# sensors.net
KiCad netlist of a schematic drawn in Altium Designer
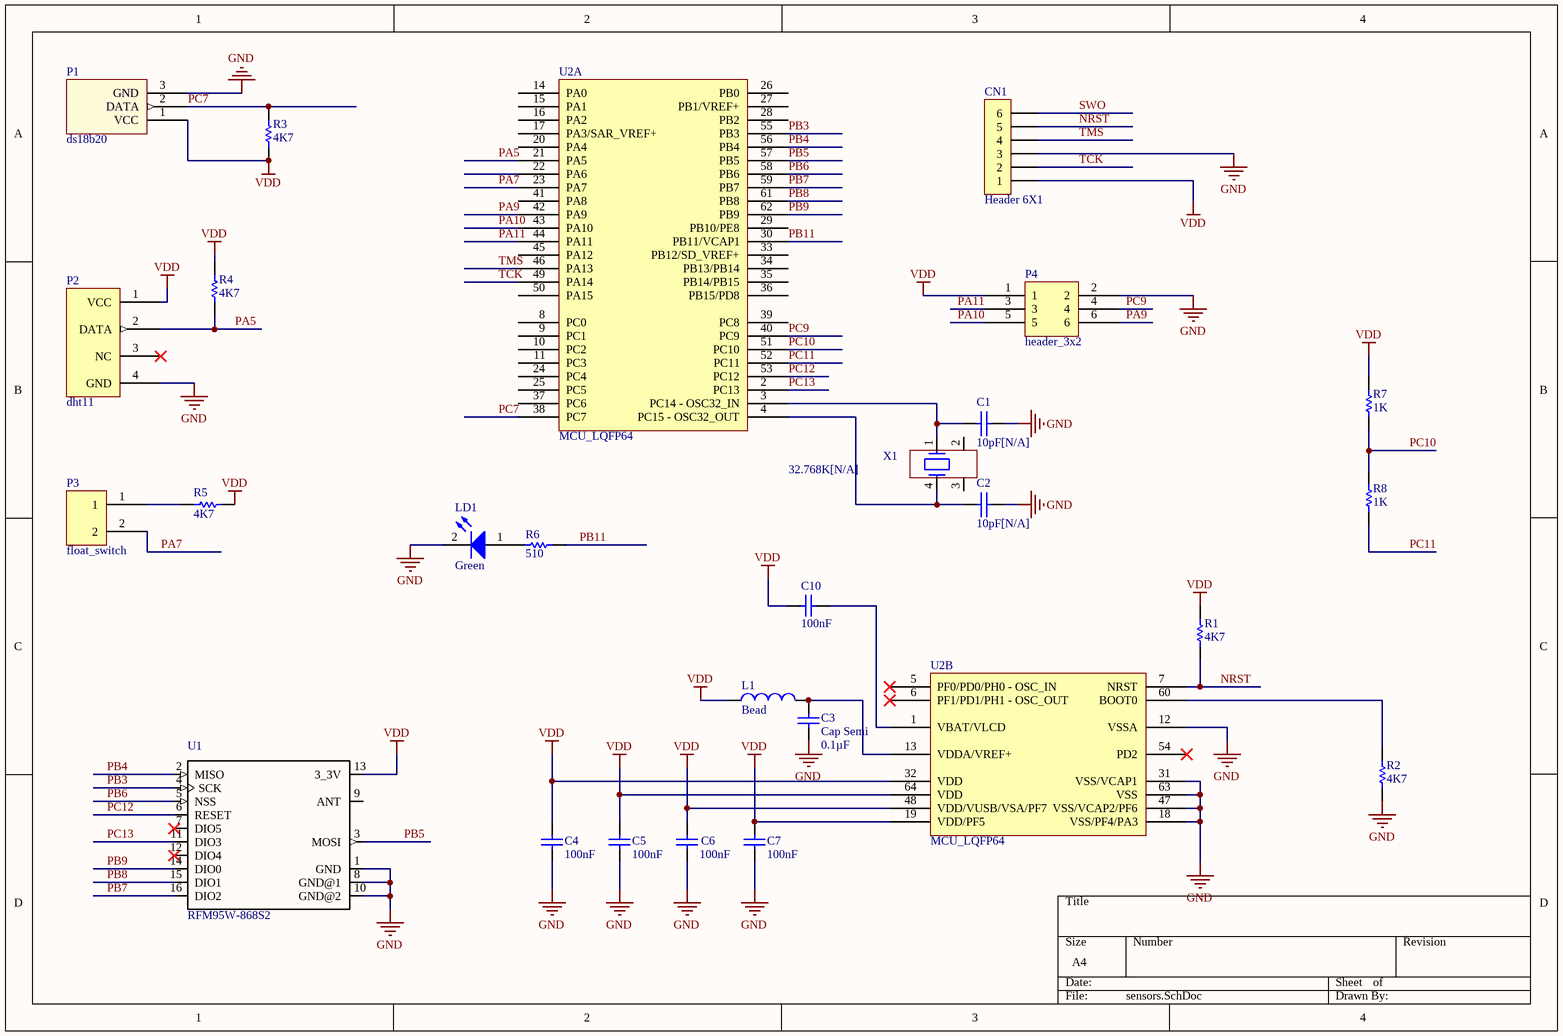
[diagram p0: sensors.SchDoc]

(export (version "E")
  (design (tool "Eeschema 10.0.6"))
  (components
    (comp (ref "C1")
      (value "10pF[N/A]")
      (footprint "0603C")
      (description "Capacitor")
      (fields (field (name "MANUFACTURER") "Murata Electronics North America"))
      (libsource (lib "MB1136") (part "CAP"))
    )
    (comp (ref "C2")
      (value "10pF[N/A]")
      (footprint "0603C")
      (description "Capacitor")
      (fields (field (name "MANUFACTURER") "Murata Electronics North America"))
      (libsource (lib "*") (part "CAP"))
    )
    (comp (ref "C3")
      (value "Cap Semi")
      (footprint "1608[0603]")
      (description "Capacitor (Semiconductor SIM Model)")
      (fields
        (field (name "ALTIUM_VALUE") "0.1µF")
        (field (name "MANUFACTURER") "AVX Corporation")
        (field (name "PUBLISHER") "Altium Limited")
      )
      (libsource (lib "Miscellaneous Devices") (part "Cap Semi"))
    )
    (comp (ref "C4")
      (value "100nF")
      (footprint "0603C")
      (description "Capacitor")
      (fields (field (name "MANUFACTURER") "AVX Corporation") (field (name "PUBLISHER") "Altium Limited"))
      (libsource (lib "Miscellaneous Devices") (part "Cap"))
    )
    (comp (ref "C5")
      (value "100nF")
      (footprint "0603C")
      (description "Capacitor")
      (fields (field (name "MANUFACTURER") "AVX Corporation") (field (name "PUBLISHER") "Altium Limited"))
      (libsource (lib "Miscellaneous Devices") (part "Cap"))
    )
    (comp (ref "C6")
      (value "100nF")
      (footprint "0603C")
      (description "Capacitor")
      (fields (field (name "MANUFACTURER") "AVX Corporation") (field (name "PUBLISHER") "Altium Limited"))
      (libsource (lib "Miscellaneous Devices") (part "Cap"))
    )
    (comp (ref "C7")
      (value "100nF")
      (footprint "0603C")
      (description "Capacitor")
      (fields (field (name "MANUFACTURER") "AVX Corporation") (field (name "PUBLISHER") "Altium Limited"))
      (libsource (lib "Miscellaneous Devices") (part "Cap"))
    )
    (comp (ref "C10")
      (value "100nF")
      (footprint "0603C")
      (description "Capacitor")
      (fields (field (name "MANUFACTURER") "AVX Corporation") (field (name "PUBLISHER") "Altium Limited"))
      (libsource (lib "Miscellaneous Devices") (part "Cap"))
    )
    (comp (ref "CN1")
      (value "Header 6X1")
      (footprint "1*6P")
      (description "Header, 6-Pin, Single row")
      (fields (field (name "MANUFACTURER") "Molex") (field (name "PUBLISHER") "Altium Limited"))
      (libsource (lib "MB1136") (part "Header 6X1"))
    )
    (comp (ref "L1")
      (value "Bead")
      (footprint "INDC1608L")
      (description "Inductor")
      (fields (field (name "MANUFACTURER") "Taiyo Yuden") (field (name "PUBLISHER") "Altium Limited"))
      (libsource (lib "Miscellaneous Devices") (part "Inductor"))
    )
    (comp (ref "LD1")
      (value "Green")
      (footprint "0603D")
      (description "Typical RED, GREEN, YELLOW, AMBER GaAs LED")
      (fields (field (name "MANUFACTURER") "Lite-On") (field (name "PUBLISHER") "Altium Limited"))
      (libsource (lib "Miscellaneous Devices") (part "LED2"))
    )
    (comp (ref "P1")
      (value "ds18b20")
      (footprint "ds18b20")
      (fields (field (name "MANUFACTURER") "Wurth Electronics"))
      (libsource (lib "seeds") (part "ds18b20"))
    )
    (comp (ref "P2") (value "dht11") (footprint "seeds:dht11") (libsource (lib "seeds") (part "dht11")))
    (comp (ref "P3")
      (value "float_switch")
      (footprint "float_switch")
      (fields (field (name "MANUFACTURER") "Harwin Inc."))
      (libsource (lib "seeds") (part "float_switch"))
    )
    (comp (ref "P4")
      (value "header_3x2")
      (footprint "header_3x2")
      (fields (field (name "MANUFACTURER") "Amphenol FCI"))
      (libsource (lib "seeds") (part "header_3x2"))
    )
    (comp (ref "R1")
      (value "4K7")
      (footprint "0603R")
      (description "Resistor")
      (fields (field (name "MANUFACTURER") "Yageo") (field (name "PUBLISHER") "Altium Limited"))
      (libsource (lib "MB1136") (part "Res1"))
    )
    (comp (ref "R2")
      (value "4K7")
      (footprint "0603R")
      (description "Resistor")
      (fields (field (name "MANUFACTURER") "Yageo") (field (name "PUBLISHER") "Altium Limited"))
      (libsource (lib "MB1136") (part "Res1"))
    )
    (comp (ref "R3")
      (value "4K7")
      (footprint "0603R")
      (description "Resistor")
      (fields (field (name "MANUFACTURER") "Yageo") (field (name "PUBLISHER") "Altium Limited"))
      (libsource (lib "MB1136") (part "Res1"))
    )
    (comp (ref "R4")
      (value "4K7")
      (footprint "0603R")
      (description "Resistor")
      (fields (field (name "MANUFACTURER") "Yageo") (field (name "PUBLISHER") "Altium Limited"))
      (libsource (lib "MB1136") (part "Res1"))
    )
    (comp (ref "R5")
      (value "4K7")
      (footprint "0603R")
      (description "Resistor")
      (fields (field (name "MANUFACTURER") "Yageo") (field (name "PUBLISHER") "Altium Limited"))
      (libsource (lib "MB1136") (part "Res1"))
    )
    (comp (ref "R6")
      (value "510")
      (footprint "0603R")
      (description "Resistor")
      (fields (field (name "MANUFACTURER") "Rohm Semiconductor") (field (name "PUBLISHER") "Altium Limited"))
      (libsource (lib "Miscellaneous Devices") (part "Res1"))
    )
    (comp (ref "R7")
      (value "1K")
      (footprint "0603R")
      (description "Resistor")
      (fields (field (name "MANUFACTURER") "Susumu") (field (name "PUBLISHER") "Altium Limited"))
      (libsource (lib "MB1136") (part "Res1"))
    )
    (comp (ref "R8")
      (value "1K")
      (footprint "0603R")
      (description "Resistor")
      (fields (field (name "MANUFACTURER") "Susumu") (field (name "PUBLISHER") "Altium Limited"))
      (libsource (lib "MB1136") (part "Res1"))
    )
    (comp (ref "U1")
      (value "RFM95W-868S2")
      (footprint "XCVR_RFM95W-868S2")
      (fields (field (name "MF") "Hope Microelectronics") (field (name "MANUFACTURER") "RF Solutions"))
      (libsource (lib "RFM95W-868S2") (part "RFM95W-868S2"))
    )
    (comp (ref "U2")
      (value "MCU_LQFP64")
      (footprint "LQFP64")
      (fields (field (name "MANUFACTURER") "STM"))
      (libsource (lib "MB1136") (part "MCU_LQFP64"))
    )
    (comp (ref "X1") (value "32.768K[N/A]") (footprint "XTAL_4SM_8X3R8") (libsource (lib "*") (part "MC306")))
  )
  (nets
    (net (code "1") (name "/NRST") (class "Default")
      (node (ref "CN1") (pin "5") (pinfunction "5_5") (pintype "passive"))
      (node (ref "R1") (pin "1") (pinfunction "1_1") (pintype "passive"))
      (node (ref "U2") (pin "7") (pinfunction "NRST_7") (pintype "passive"))
    )
    (net (code "2") (name "/PA5") (class "Default")
      (node (ref "P2") (pin "2") (pinfunction "DATA_2") (pintype "output"))
      (node (ref "R4") (pin "2") (pinfunction "2_2") (pintype "passive"))
      (node (ref "U2") (pin "21") (pinfunction "PA5_21") (pintype "passive"))
    )
    (net (code "3") (name "/PA7") (class "Default")
      (node (ref "P3") (pin "2") (pinfunction "2_2") (pintype "passive"))
      (node (ref "U2") (pin "23") (pinfunction "PA7_23") (pintype "passive"))
    )
    (net (code "4") (name "/PA9") (class "Default")
      (node (ref "P4") (pin "6") (pinfunction "6_6") (pintype "passive"))
      (node (ref "U2") (pin "42") (pinfunction "PA9_42") (pintype "passive"))
    )
    (net (code "5") (name "/PA10") (class "Default")
      (node (ref "P4") (pin "5") (pinfunction "5_5") (pintype "passive"))
      (node (ref "U2") (pin "43") (pinfunction "PA10_43") (pintype "passive"))
    )
    (net (code "6") (name "/PA11") (class "Default")
      (node (ref "P4") (pin "3") (pinfunction "3_3") (pintype "passive"))
      (node (ref "U2") (pin "44") (pinfunction "PA11_44") (pintype "passive"))
    )
    (net (code "7") (name "/PB3") (class "Default")
      (node (ref "U1") (pin "4") (pinfunction "SCK_4") (pintype "input"))
      (node (ref "U2") (pin "55") (pinfunction "PB3_55") (pintype "passive"))
    )
    (net (code "8") (name "/PB4") (class "Default")
      (node (ref "U1") (pin "2") (pinfunction "MISO_2") (pintype "input"))
      (node (ref "U2") (pin "56") (pinfunction "PB4_56") (pintype "passive"))
    )
    (net (code "9") (name "/PB5") (class "Default")
      (node (ref "U1") (pin "3") (pinfunction "MOSI_3") (pintype "output"))
      (node (ref "U2") (pin "57") (pinfunction "PB5_57") (pintype "passive"))
    )
    (net (code "10") (name "/PB6") (class "Default")
      (node (ref "U1") (pin "5") (pinfunction "NSS_5") (pintype "input"))
      (node (ref "U2") (pin "58") (pinfunction "PB6_58") (pintype "passive"))
    )
    (net (code "11") (name "/PB7") (class "Default")
      (node (ref "U1") (pin "16") (pinfunction "DIO2_16") (pintype "bidirectional"))
      (node (ref "U2") (pin "59") (pinfunction "PB7_59") (pintype "passive"))
    )
    (net (code "12") (name "/PB8") (class "Default")
      (node (ref "U1") (pin "15") (pinfunction "DIO1_15") (pintype "bidirectional"))
      (node (ref "U2") (pin "61") (pinfunction "PB8_61") (pintype "passive"))
    )
    (net (code "13") (name "/PB9") (class "Default")
      (node (ref "U1") (pin "14") (pinfunction "DIO0_14") (pintype "bidirectional"))
      (node (ref "U2") (pin "62") (pinfunction "PB9_62") (pintype "passive"))
    )
    (net (code "14") (name "/PB11") (class "Default")
      (node (ref "R6") (pin "1") (pinfunction "1_1") (pintype "passive"))
      (node (ref "U2") (pin "30") (pinfunction "PB11/VCAP1_30") (pintype "passive"))
    )
    (net (code "15") (name "/PC7") (class "Default")
      (node (ref "P1") (pin "2") (pinfunction "DATA_2") (pintype "output"))
      (node (ref "R3") (pin "1") (pinfunction "1_1") (pintype "passive"))
      (node (ref "U2") (pin "38") (pinfunction "PC7_38") (pintype "passive"))
    )
    (net (code "16") (name "/PC9") (class "Default")
      (node (ref "P4") (pin "4") (pinfunction "4_4") (pintype "passive"))
      (node (ref "U2") (pin "40") (pinfunction "PC9_40") (pintype "passive"))
    )
    (net (code "17") (name "/PC10") (class "Default")
      (node (ref "R7") (pin "2") (pinfunction "2_2") (pintype "passive"))
      (node (ref "R8") (pin "1") (pinfunction "1_1") (pintype "passive"))
      (node (ref "U2") (pin "51") (pinfunction "PC10_51") (pintype "passive"))
    )
    (net (code "18") (name "/PC11") (class "Default")
      (node (ref "R8") (pin "2") (pinfunction "2_2") (pintype "passive"))
      (node (ref "U2") (pin "52") (pinfunction "PC11_52") (pintype "passive"))
    )
    (net (code "19") (name "/PC12") (class "Default")
      (node (ref "U1") (pin "6") (pinfunction "RESET_6") (pintype "bidirectional"))
      (node (ref "U2") (pin "53") (pinfunction "PC12_53") (pintype "passive"))
    )
    (net (code "20") (name "/PC13") (class "Default")
      (node (ref "U1") (pin "11") (pinfunction "DIO3_11") (pintype "bidirectional"))
      (node (ref "U2") (pin "2") (pinfunction "PC13_2") (pintype "passive"))
    )
    (net (code "21") (name "/SWO") (class "Default")
      (node (ref "CN1") (pin "6") (pinfunction "6_6") (pintype "passive"))
    )
    (net (code "22") (name "/TCK") (class "Default")
      (node (ref "CN1") (pin "2") (pinfunction "2_2") (pintype "passive"))
      (node (ref "U2") (pin "49") (pinfunction "PA14_49") (pintype "passive"))
    )
    (net (code "23") (name "/TMS") (class "Default")
      (node (ref "CN1") (pin "4") (pinfunction "4_4") (pintype "passive"))
      (node (ref "U2") (pin "46") (pinfunction "PA13_46") (pintype "passive"))
    )
    (net (code "24") (name "GND") (class "Default")
      (node (ref "C1") (pin "2") (pinfunction "2_2") (pintype "passive"))
      (node (ref "C2") (pin "2") (pinfunction "2_2") (pintype "passive"))
      (node (ref "C3") (pin "2") (pinfunction "2_2") (pintype "passive"))
      (node (ref "C4") (pin "2") (pinfunction "2_2") (pintype "passive"))
      (node (ref "C5") (pin "2") (pinfunction "2_2") (pintype "passive"))
      (node (ref "C6") (pin "2") (pinfunction "2_2") (pintype "passive"))
      (node (ref "C7") (pin "2") (pinfunction "2_2") (pintype "passive"))
      (node (ref "CN1") (pin "3") (pinfunction "3_3") (pintype "passive"))
      (node (ref "LD1") (pin "2") (pinfunction "K_2") (pintype "passive"))
      (node (ref "P1") (pin "3") (pinfunction "GND_3") (pintype "power_in"))
      (node (ref "P2") (pin "4") (pinfunction "GND_4") (pintype "power_in"))
      (node (ref "P4") (pin "2") (pinfunction "2_2") (pintype "passive"))
      (node (ref "R2") (pin "1") (pinfunction "1_1") (pintype "passive"))
      (node (ref "U1") (pin "1") (pinfunction "GND_1") (pintype "power_in"))
      (node (ref "U1") (pin "10") (pinfunction "GND@2_10") (pintype "power_in"))
      (node (ref "U1") (pin "8") (pinfunction "GND@1_8") (pintype "power_in"))
      (node (ref "U2") (pin "12") (pinfunction "VSSA_12") (pintype "passive"))
      (node (ref "U2") (pin "18") (pinfunction "VSS/PF4/PA3_18") (pintype "passive"))
      (node (ref "U2") (pin "31") (pinfunction "VSS/VCAP1_31") (pintype "passive"))
      (node (ref "U2") (pin "47") (pinfunction "VSS/VCAP2/PF6_47") (pintype "passive"))
      (node (ref "U2") (pin "63") (pinfunction "VSS_63") (pintype "passive"))
    )
    (net (code "25") (name "Net-(LD1-A)") (class "Default")
      (node (ref "LD1") (pin "1") (pinfunction "A_1") (pintype "passive"))
      (node (ref "R6") (pin "2") (pinfunction "2_2") (pintype "passive"))
    )
    (net (code "26") (name "Net-(P3-Pad1)") (class "Default")
      (node (ref "P3") (pin "1") (pinfunction "1_1") (pintype "passive"))
      (node (ref "R5") (pin "2") (pinfunction "2_2") (pintype "passive"))
    )
    (net (code "27") (name "Net-(U2A-PC14_-_OSC32_IN)") (class "Default")
      (node (ref "C1") (pin "1") (pinfunction "1_1") (pintype "passive"))
      (node (ref "U2") (pin "3") (pinfunction "PC14_-_OSC32_IN_3") (pintype "passive"))
      (node (ref "X1") (pin "1") (pinfunction "1_1") (pintype "passive"))
    )
    (net (code "28") (name "Net-(U2A-PC15_-_OSC32_OUT)") (class "Default")
      (node (ref "C2") (pin "1") (pinfunction "1_1") (pintype "passive"))
      (node (ref "U2") (pin "4") (pinfunction "PC15_-_OSC32_OUT_4") (pintype "passive"))
      (node (ref "X1") (pin "4") (pinfunction "4_4") (pintype "passive"))
    )
    (net (code "29") (name "Net-(U2B-BOOT0)") (class "Default")
      (node (ref "R2") (pin "2") (pinfunction "2_2") (pintype "passive"))
      (node (ref "U2") (pin "60") (pinfunction "BOOT0_60") (pintype "passive"))
    )
    (net (code "30") (name "Net-(U2B-VBAT{slash}VLCD)") (class "Default")
      (node (ref "C10") (pin "2") (pinfunction "2_2") (pintype "passive"))
      (node (ref "U2") (pin "1") (pinfunction "VBAT/VLCD_1") (pintype "passive"))
    )
    (net (code "31") (name "Net-(U2B-VDDA{slash}VREF+)") (class "Default")
      (node (ref "C3") (pin "1") (pinfunction "1_1") (pintype "passive"))
      (node (ref "L1") (pin "2") (pinfunction "2_2") (pintype "passive"))
      (node (ref "U2") (pin "13") (pinfunction "VDDA/VREF+_13") (pintype "passive"))
    )
    (net (code "32") (name "VDD") (class "Default")
      (node (ref "C10") (pin "1") (pinfunction "1_1") (pintype "passive"))
      (node (ref "C4") (pin "1") (pinfunction "1_1") (pintype "passive"))
      (node (ref "C5") (pin "1") (pinfunction "1_1") (pintype "passive"))
      (node (ref "C6") (pin "1") (pinfunction "1_1") (pintype "passive"))
      (node (ref "C7") (pin "1") (pinfunction "1_1") (pintype "passive"))
      (node (ref "CN1") (pin "1") (pinfunction "1_1") (pintype "passive"))
      (node (ref "L1") (pin "1") (pinfunction "1_1") (pintype "passive"))
      (node (ref "P1") (pin "1") (pinfunction "VCC_1") (pintype "power_in"))
      (node (ref "P2") (pin "1") (pinfunction "VCC_1") (pintype "power_in"))
      (node (ref "P4") (pin "1") (pinfunction "1_1") (pintype "passive"))
      (node (ref "R1") (pin "2") (pinfunction "2_2") (pintype "passive"))
      (node (ref "R3") (pin "2") (pinfunction "2_2") (pintype "passive"))
      (node (ref "R4") (pin "1") (pinfunction "1_1") (pintype "passive"))
      (node (ref "R5") (pin "1") (pinfunction "1_1") (pintype "passive"))
      (node (ref "R7") (pin "1") (pinfunction "1_1") (pintype "passive"))
      (node (ref "U1") (pin "13") (pinfunction "3_3V_13") (pintype "power_in"))
      (node (ref "U2") (pin "19") (pinfunction "VDD/PF5_19") (pintype "passive"))
      (node (ref "U2") (pin "32") (pinfunction "VDD_32") (pintype "passive"))
      (node (ref "U2") (pin "48") (pinfunction "VDD/VUSB/VSA/PF7_48") (pintype "passive"))
      (node (ref "U2") (pin "64") (pinfunction "VDD_64") (pintype "passive"))
    )
    (net (code "33") (name "unconnected-(P2-NC-Pad3)") (class "Default")
      (node (ref "P2") (pin "3") (pinfunction "NC_3") (pintype "passive+no_connect"))
    )
    (net (code "34") (name "unconnected-(U1-ANT-Pad9)") (class "Default")
      (node (ref "U1") (pin "9") (pinfunction "ANT_9") (pintype "passive"))
    )
    (net (code "35") (name "unconnected-(U1-DIO4-Pad12)") (class "Default")
      (node (ref "U1") (pin "12") (pinfunction "DIO4_12") (pintype "bidirectional+no_connect"))
    )
    (net (code "36") (name "unconnected-(U1-DIO5-Pad7)") (class "Default")
      (node (ref "U1") (pin "7") (pinfunction "DIO5_7") (pintype "bidirectional+no_connect"))
    )
    (net (code "37") (name "unconnected-(U2A-PA0-Pad14)") (class "Default")
      (node (ref "U2") (pin "14") (pinfunction "PA0_14") (pintype "passive"))
    )
    (net (code "38") (name "unconnected-(U2A-PA1-Pad15)") (class "Default")
      (node (ref "U2") (pin "15") (pinfunction "PA1_15") (pintype "passive"))
    )
    (net (code "39") (name "unconnected-(U2A-PA2-Pad16)") (class "Default")
      (node (ref "U2") (pin "16") (pinfunction "PA2_16") (pintype "passive"))
    )
    (net (code "40") (name "unconnected-(U2A-PA3{slash}SAR_VREF+-Pad17)") (class "Default")
      (node (ref "U2") (pin "17") (pinfunction "PA3/SAR_VREF+_17") (pintype "passive"))
    )
    (net (code "41") (name "unconnected-(U2A-PA4-Pad20)") (class "Default")
      (node (ref "U2") (pin "20") (pinfunction "PA4_20") (pintype "passive"))
    )
    (net (code "42") (name "unconnected-(U2A-PA6-Pad22)") (class "Default")
      (node (ref "U2") (pin "22") (pinfunction "PA6_22") (pintype "passive"))
    )
    (net (code "43") (name "unconnected-(U2A-PA8-Pad41)") (class "Default")
      (node (ref "U2") (pin "41") (pinfunction "PA8_41") (pintype "passive"))
    )
    (net (code "44") (name "unconnected-(U2A-PA12-Pad45)") (class "Default")
      (node (ref "U2") (pin "45") (pinfunction "PA12_45") (pintype "passive"))
    )
    (net (code "45") (name "unconnected-(U2A-PA15-Pad50)") (class "Default")
      (node (ref "U2") (pin "50") (pinfunction "PA15_50") (pintype "passive"))
    )
    (net (code "46") (name "unconnected-(U2A-PB0-Pad26)") (class "Default")
      (node (ref "U2") (pin "26") (pinfunction "PB0_26") (pintype "passive"))
    )
    (net (code "47") (name "unconnected-(U2A-PB1{slash}VREF+-Pad27)") (class "Default")
      (node (ref "U2") (pin "27") (pinfunction "PB1/VREF+_27") (pintype "passive"))
    )
    (net (code "48") (name "unconnected-(U2A-PB2-Pad28)") (class "Default")
      (node (ref "U2") (pin "28") (pinfunction "PB2_28") (pintype "passive"))
    )
    (net (code "49") (name "unconnected-(U2A-PB10{slash}PE8-Pad29)") (class "Default")
      (node (ref "U2") (pin "29") (pinfunction "PB10/PE8_29") (pintype "passive"))
    )
    (net (code "50") (name "unconnected-(U2A-PB12{slash}SD_VREF+-Pad33)") (class "Default")
      (node (ref "U2") (pin "33") (pinfunction "PB12/SD_VREF+_33") (pintype "passive"))
    )
    (net (code "51") (name "unconnected-(U2A-PB13{slash}PB14-Pad34)") (class "Default")
      (node (ref "U2") (pin "34") (pinfunction "PB13/PB14_34") (pintype "passive"))
    )
    (net (code "52") (name "unconnected-(U2A-PB14{slash}PB15-Pad35)") (class "Default")
      (node (ref "U2") (pin "35") (pinfunction "PB14/PB15_35") (pintype "passive"))
    )
    (net (code "53") (name "unconnected-(U2A-PB15{slash}PD8-Pad36)") (class "Default")
      (node (ref "U2") (pin "36") (pinfunction "PB15/PD8_36") (pintype "passive"))
    )
    (net (code "54") (name "unconnected-(U2A-PC0-Pad8)") (class "Default")
      (node (ref "U2") (pin "8") (pinfunction "PC0_8") (pintype "passive"))
    )
    (net (code "55") (name "unconnected-(U2A-PC1-Pad9)") (class "Default")
      (node (ref "U2") (pin "9") (pinfunction "PC1_9") (pintype "passive"))
    )
    (net (code "56") (name "unconnected-(U2A-PC2-Pad10)") (class "Default")
      (node (ref "U2") (pin "10") (pinfunction "PC2_10") (pintype "passive"))
    )
    (net (code "57") (name "unconnected-(U2A-PC3-Pad11)") (class "Default")
      (node (ref "U2") (pin "11") (pinfunction "PC3_11") (pintype "passive"))
    )
    (net (code "58") (name "unconnected-(U2A-PC4-Pad24)") (class "Default")
      (node (ref "U2") (pin "24") (pinfunction "PC4_24") (pintype "passive"))
    )
    (net (code "59") (name "unconnected-(U2A-PC5-Pad25)") (class "Default")
      (node (ref "U2") (pin "25") (pinfunction "PC5_25") (pintype "passive"))
    )
    (net (code "60") (name "unconnected-(U2A-PC6-Pad37)") (class "Default")
      (node (ref "U2") (pin "37") (pinfunction "PC6_37") (pintype "passive"))
    )
    (net (code "61") (name "unconnected-(U2A-PC8-Pad39)") (class "Default")
      (node (ref "U2") (pin "39") (pinfunction "PC8_39") (pintype "passive"))
    )
    (net (code "62") (name "unconnected-(U2B-PD2-Pad54)") (class "Default")
      (node (ref "U2") (pin "54") (pinfunction "PD2_54") (pintype "passive+no_connect"))
    )
    (net (code "63") (name "unconnected-(U2B-PF0{slash}PD0{slash}PH0_-_OSC_IN-Pad5)") (class "Default")
      (node (ref "U2") (pin "5") (pinfunction "PF0/PD0/PH0_-_OSC_IN_5") (pintype "passive+no_connect"))
    )
    (net (code "64") (name "unconnected-(U2B-PF1{slash}PD1{slash}PH1_-_OSC_OUT-Pad6)") (class "Default")
      (node (ref "U2") (pin "6") (pinfunction "PF1/PD1/PH1_-_OSC_OUT_6") (pintype "passive+no_connect"))
    )
    (net (code "65") (name "unconnected-(X1-Pad2)") (class "Default")
      (node (ref "X1") (pin "2") (pinfunction "2_2") (pintype "passive"))
    )
    (net (code "66") (name "unconnected-(X1-Pad3)") (class "Default")
      (node (ref "X1") (pin "3") (pinfunction "3_3") (pintype "passive"))
    )
  )
)
